# schema.net
KiCad netlist of a schematic drawn in EAGLE
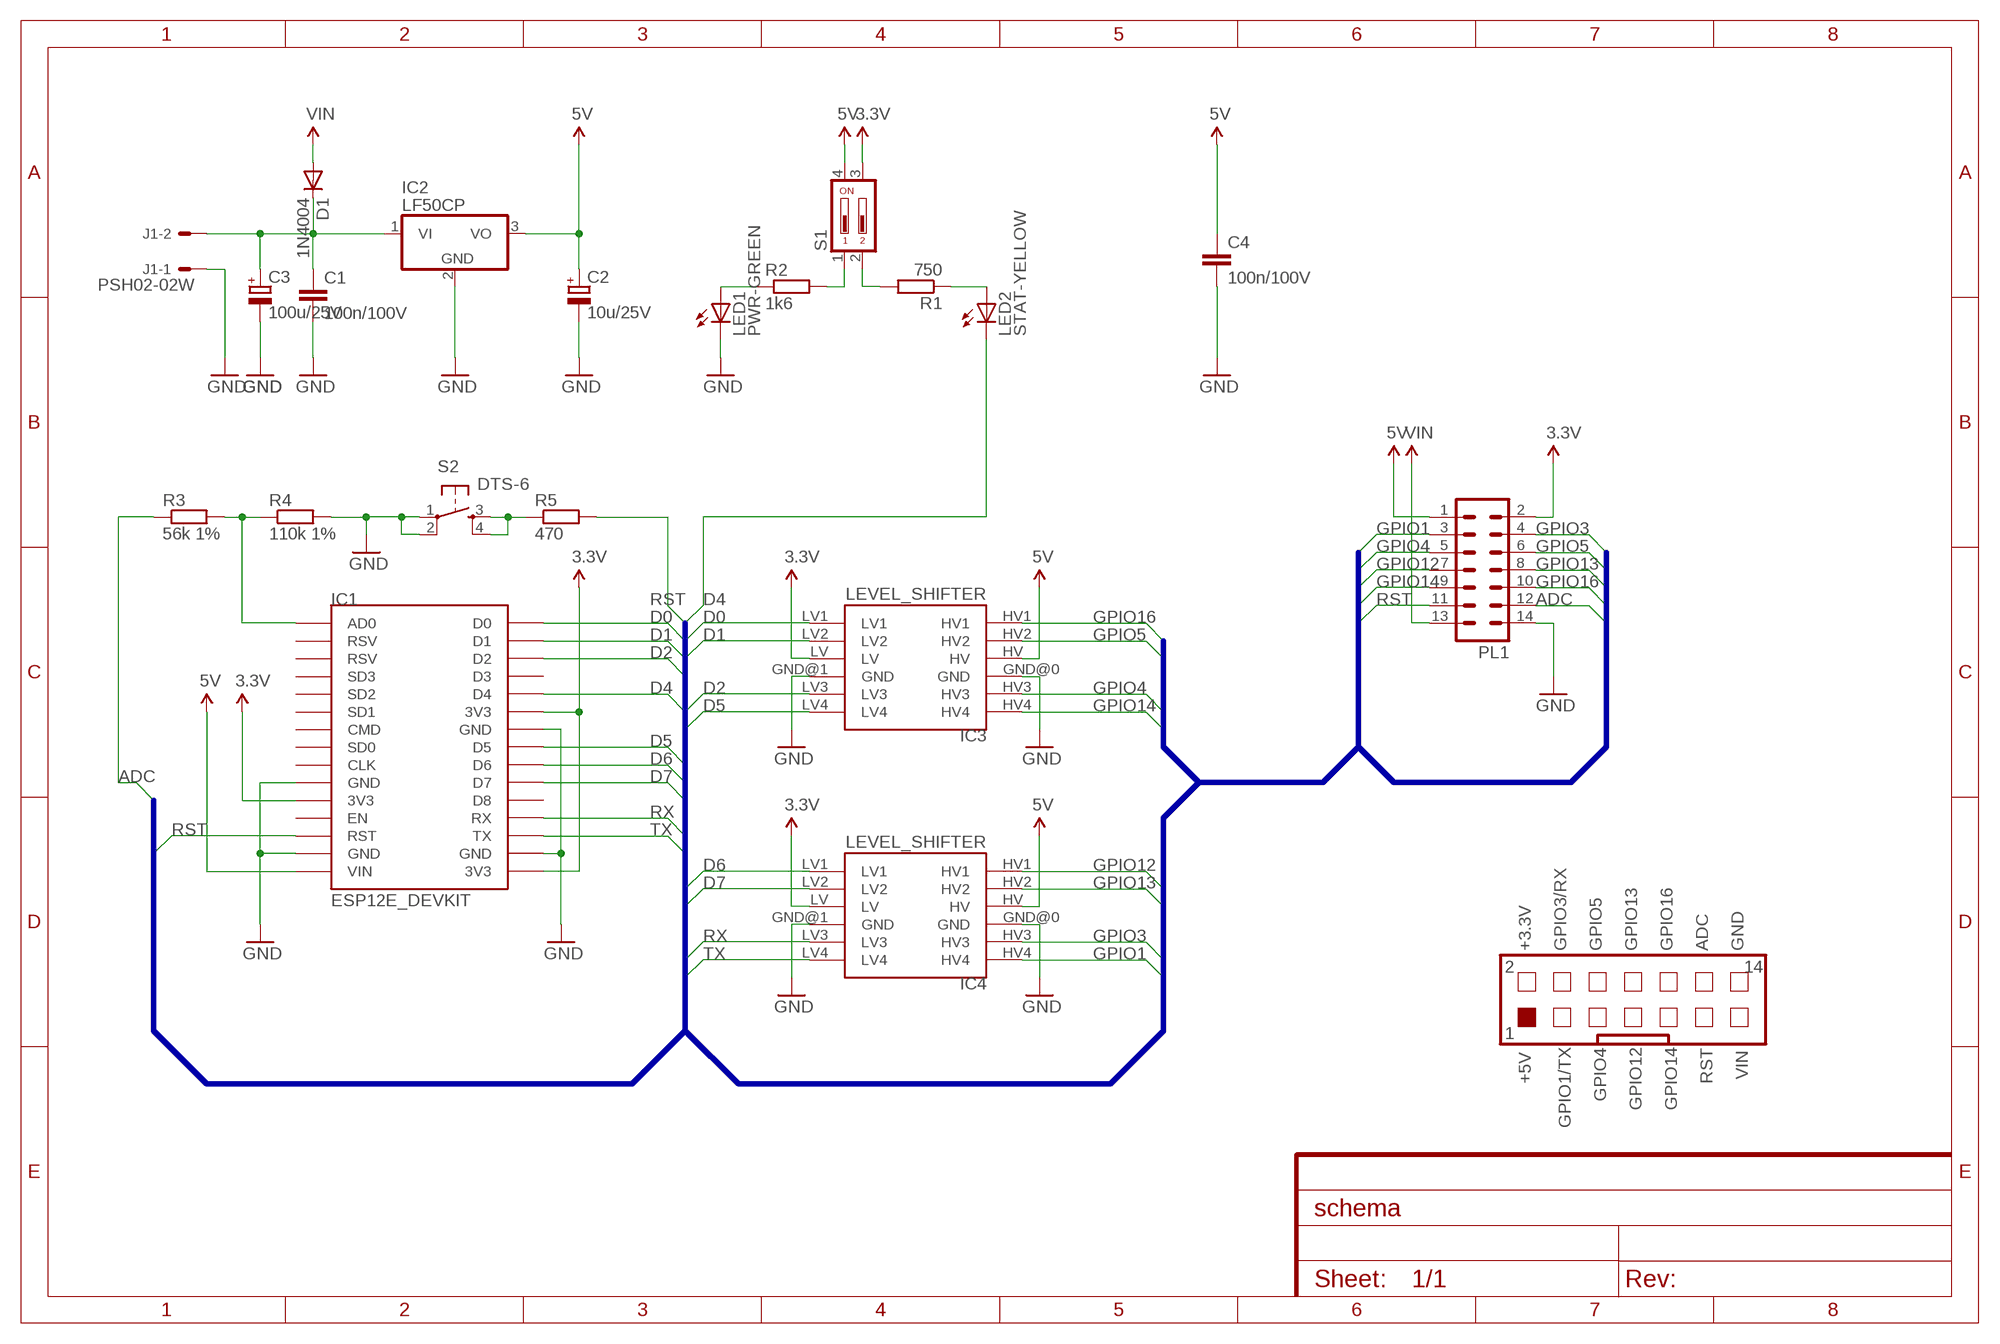
[diagram p0: schematic, sheet 1]

(export (version "E")
  (design (tool "Eeschema 10.0.6"))
  (components
    (comp (ref "C1")
      (value "100n/100V")
      (footprint "eagle-import:C025-025X050")
      (libsource (lib "eagle-import") (part "C-EUC025-025X050"))
    )
    (comp (ref "C2")
      (value "10u/25V")
      (footprint "eagle-import:E3,5-8")
      (libsource (lib "eagle-import") (part "CPOL-EUE3,5-8"))
    )
    (comp (ref "C3")
      (value "100u/25V")
      (footprint "eagle-import:E5-13")
      (libsource (lib "eagle-import") (part "CPOL-EUE5-13"))
    )
    (comp (ref "C4")
      (value "100n/100V")
      (footprint "eagle-import:C025-025X050")
      (libsource (lib "eagle-import") (part "C-EUC025-025X050"))
    )
    (comp (ref "D1")
      (value "1N4004")
      (footprint "eagle-import:DO41-10")
      (libsource (lib "eagle-import") (part "1N4004"))
    )
    (comp (ref "IC1")
      (value "ESP12E_DEVKIT")
      (footprint "eagle-import:ESP12E_DEVKIT")
      (libsource (lib "eagle-import") (part "ESP12E_DEVKIT"))
    )
    (comp (ref "IC2")
      (value "LF50CP")
      (footprint "eagle-import:TO220H")
      (libsource (lib "eagle-import") (part "LF50CP"))
    )
    (comp (ref "IC3")
      (value "LEVEL_SHIFTER")
      (footprint "eagle-import:LEVEL_SHIFTER")
      (libsource (lib "eagle-import") (part "LEVEL_SHIFTER"))
    )
    (comp (ref "IC4")
      (value "LEVEL_SHIFTER")
      (footprint "eagle-import:LEVEL_SHIFTER")
      (libsource (lib "eagle-import") (part "LEVEL_SHIFTER"))
    )
    (comp (ref "J1")
      (value "PSH02-02W")
      (footprint "eagle-import:7395-02")
      (libsource (lib "eagle-import") (part "22-?-0205-7028"))
    )
    (comp (ref "LED1")
      (value "PWR-GREEN")
      (footprint "eagle-import:LED3MM")
      (libsource (lib "eagle-import") (part "LED3MM"))
    )
    (comp (ref "LED2")
      (value "STAT-YELLOW")
      (footprint "eagle-import:LED3MM")
      (libsource (lib "eagle-import") (part "LED3MM"))
    )
    (comp (ref "PL1")
      (value "14V")
      (footprint "eagle-import:14V")
      (libsource (lib "eagle-import") (part "14V"))
    )
    (comp (ref "R1")
      (value "750")
      (footprint "eagle-import:R1206")
      (libsource (lib "eagle-import") (part "R-EU_R1206"))
    )
    (comp (ref "R2")
      (value "1k6")
      (footprint "eagle-import:R1206")
      (libsource (lib "eagle-import") (part "R-EU_R1206"))
    )
    (comp (ref "R3")
      (value "56k 1%")
      (footprint "eagle-import:R1206")
      (libsource (lib "eagle-import") (part "R-EU_R1206"))
    )
    (comp (ref "R4")
      (value "110k 1%")
      (footprint "eagle-import:R1206")
      (libsource (lib "eagle-import") (part "R-EU_R1206"))
    )
    (comp (ref "R5")
      (value "470")
      (footprint "eagle-import:R1206")
      (libsource (lib "eagle-import") (part "R-EU_R1206"))
    )
    (comp (ref "S1")
      (value "DIP02YL")
      (footprint "eagle-import:DIP02YL")
      (libsource (lib "eagle-import") (part "DIP02YL"))
    )
    (comp (ref "S2")
      (value "DTS-6")
      (footprint "eagle-import:DTS-6")
      (libsource (lib "eagle-import") (part "DTS-6"))
    )
  )
  (nets
    (net (code "1") (name "/ADC") (class "Default")
      (node (ref "PL1") (pin "12") (pinfunction "12_12") (pintype "passive"))
      (node (ref "R3") (pin "1") (pinfunction "1_1") (pintype "passive"))
    )
    (net (code "2") (name "/D0") (class "Default")
      (node (ref "IC1") (pin "D0") (pinfunction "D0_D0") (pintype "bidirectional"))
      (node (ref "IC3") (pin "LV1") (pinfunction "LV1_LV1") (pintype "bidirectional"))
    )
    (net (code "3") (name "/D1") (class "Default")
      (node (ref "IC1") (pin "D1") (pinfunction "D1_D1") (pintype "bidirectional"))
      (node (ref "IC3") (pin "LV2") (pinfunction "LV2_LV2") (pintype "bidirectional"))
    )
    (net (code "4") (name "/D2") (class "Default")
      (node (ref "IC1") (pin "D2") (pinfunction "D2_D2") (pintype "bidirectional"))
      (node (ref "IC3") (pin "LV3") (pinfunction "LV3_LV3") (pintype "bidirectional"))
    )
    (net (code "5") (name "/D4") (class "Default")
      (node (ref "IC1") (pin "D4") (pinfunction "D4_D4") (pintype "bidirectional"))
      (node (ref "LED2") (pin "K") (pinfunction "C_K") (pintype "passive"))
    )
    (net (code "6") (name "/D5") (class "Default")
      (node (ref "IC1") (pin "D5") (pinfunction "D5_D5") (pintype "bidirectional"))
      (node (ref "IC3") (pin "LV4") (pinfunction "LV4_LV4") (pintype "bidirectional"))
    )
    (net (code "7") (name "/D6") (class "Default")
      (node (ref "IC1") (pin "D6") (pinfunction "D6_D6") (pintype "bidirectional"))
      (node (ref "IC4") (pin "LV1") (pinfunction "LV1_LV1") (pintype "bidirectional"))
    )
    (net (code "8") (name "/D7") (class "Default")
      (node (ref "IC1") (pin "D7") (pinfunction "D7_D7") (pintype "bidirectional"))
      (node (ref "IC4") (pin "LV2") (pinfunction "LV2_LV2") (pintype "bidirectional"))
    )
    (net (code "9") (name "/GPIO1") (class "Default")
      (node (ref "IC4") (pin "HV4") (pinfunction "HV4_HV4") (pintype "bidirectional"))
      (node (ref "PL1") (pin "3") (pinfunction "3_3") (pintype "passive"))
    )
    (net (code "10") (name "/GPIO3") (class "Default")
      (node (ref "IC4") (pin "HV3") (pinfunction "HV3_HV3") (pintype "bidirectional"))
      (node (ref "PL1") (pin "4") (pinfunction "4_4") (pintype "passive"))
    )
    (net (code "11") (name "/GPIO4") (class "Default")
      (node (ref "IC3") (pin "HV3") (pinfunction "HV3_HV3") (pintype "bidirectional"))
      (node (ref "PL1") (pin "5") (pinfunction "5_5") (pintype "passive"))
    )
    (net (code "12") (name "/GPIO5") (class "Default")
      (node (ref "IC3") (pin "HV2") (pinfunction "HV2_HV2") (pintype "bidirectional"))
      (node (ref "PL1") (pin "6") (pinfunction "6_6") (pintype "passive"))
    )
    (net (code "13") (name "/GPIO12") (class "Default")
      (node (ref "IC4") (pin "HV1") (pinfunction "HV1_HV1") (pintype "bidirectional"))
      (node (ref "PL1") (pin "7") (pinfunction "7_7") (pintype "passive"))
    )
    (net (code "14") (name "/GPIO13") (class "Default")
      (node (ref "IC4") (pin "HV2") (pinfunction "HV2_HV2") (pintype "bidirectional"))
      (node (ref "PL1") (pin "8") (pinfunction "8_8") (pintype "passive"))
    )
    (net (code "15") (name "/GPIO14") (class "Default")
      (node (ref "IC3") (pin "HV4") (pinfunction "HV4_HV4") (pintype "bidirectional"))
      (node (ref "PL1") (pin "9") (pinfunction "9_9") (pintype "passive"))
    )
    (net (code "16") (name "/GPIO16") (class "Default")
      (node (ref "IC3") (pin "HV1") (pinfunction "HV1_HV1") (pintype "bidirectional"))
      (node (ref "PL1") (pin "10") (pinfunction "10_10") (pintype "passive"))
    )
    (net (code "17") (name "/RST") (class "Default")
      (node (ref "IC1") (pin "RST") (pinfunction "RST_RST") (pintype "bidirectional"))
      (node (ref "PL1") (pin "11") (pinfunction "11_11") (pintype "passive"))
      (node (ref "R5") (pin "2") (pinfunction "2_2") (pintype "passive"))
    )
    (net (code "18") (name "/RX") (class "Default")
      (node (ref "IC1") (pin "RX") (pinfunction "RX_RX") (pintype "bidirectional"))
      (node (ref "IC4") (pin "LV3") (pinfunction "LV3_LV3") (pintype "bidirectional"))
    )
    (net (code "19") (name "/TX") (class "Default")
      (node (ref "IC1") (pin "TX") (pinfunction "TX_TX") (pintype "bidirectional"))
      (node (ref "IC4") (pin "LV4") (pinfunction "LV4_LV4") (pintype "bidirectional"))
    )
    (net (code "20") (name "3.3V") (class "Default")
      (node (ref "IC1") (pin "3V3@0") (pinfunction "3V3_3V3@0") (pintype "bidirectional"))
      (node (ref "IC1") (pin "3V3@1") (pinfunction "3V3_3V3@1") (pintype "bidirectional"))
      (node (ref "IC1") (pin "3V3@2") (pinfunction "3V3_3V3@2") (pintype "bidirectional"))
      (node (ref "IC3") (pin "LV") (pinfunction "LV_LV") (pintype "bidirectional"))
      (node (ref "IC4") (pin "LV") (pinfunction "LV_LV") (pintype "bidirectional"))
      (node (ref "PL1") (pin "2") (pinfunction "2_2") (pintype "passive"))
      (node (ref "S1") (pin "3") (pinfunction "3_3") (pintype "passive"))
    )
    (net (code "21") (name "5V") (class "Default")
      (node (ref "C2") (pin "+") (pinfunction "+_+") (pintype "passive"))
      (node (ref "C4") (pin "1") (pinfunction "1_1") (pintype "passive"))
      (node (ref "IC1") (pin "VIN") (pinfunction "VIN_VIN") (pintype "bidirectional"))
      (node (ref "IC2") (pin "3") (pinfunction "VO_3") (pintype "passive"))
      (node (ref "IC3") (pin "HV") (pinfunction "HV_HV") (pintype "bidirectional"))
      (node (ref "IC4") (pin "HV") (pinfunction "HV_HV") (pintype "bidirectional"))
      (node (ref "PL1") (pin "1") (pinfunction "1_1") (pintype "passive"))
      (node (ref "S1") (pin "4") (pinfunction "4_4") (pintype "passive"))
    )
    (net (code "22") (name "GND") (class "Default")
      (node (ref "C1") (pin "2") (pinfunction "2_2") (pintype "passive"))
      (node (ref "C2") (pin "-") (pinfunction "-_-") (pintype "passive"))
      (node (ref "C3") (pin "-") (pinfunction "-_-") (pintype "passive"))
      (node (ref "C4") (pin "2") (pinfunction "2_2") (pintype "passive"))
      (node (ref "IC1") (pin "GND@0") (pinfunction "GND_GND@0") (pintype "bidirectional"))
      (node (ref "IC1") (pin "GND@1") (pinfunction "GND_GND@1") (pintype "bidirectional"))
      (node (ref "IC1") (pin "GND@2") (pinfunction "GND_GND@2") (pintype "bidirectional"))
      (node (ref "IC1") (pin "GND@3") (pinfunction "GND_GND@3") (pintype "bidirectional"))
      (node (ref "IC2") (pin "2") (pinfunction "GND_2") (pintype "passive"))
      (node (ref "IC3") (pin "GND@0") (pinfunction "GND_GND@0") (pintype "bidirectional"))
      (node (ref "IC3") (pin "GND@1") (pinfunction "GND_GND@1") (pintype "bidirectional"))
      (node (ref "IC4") (pin "GND@0") (pinfunction "GND_GND@0") (pintype "bidirectional"))
      (node (ref "IC4") (pin "GND@1") (pinfunction "GND_GND@1") (pintype "bidirectional"))
      (node (ref "J1") (pin "1") (pinfunction "S_1") (pintype "passive"))
      (node (ref "LED1") (pin "K") (pinfunction "C_K") (pintype "passive"))
      (node (ref "PL1") (pin "14") (pinfunction "14_14") (pintype "passive"))
      (node (ref "R4") (pin "2") (pinfunction "2_2") (pintype "passive"))
      (node (ref "S2") (pin "1") (pinfunction "1_1") (pintype "passive"))
      (node (ref "S2") (pin "2") (pinfunction "2_2") (pintype "passive"))
    )
    (net (code "23") (name "Net-(IC1-PadAD0)") (class "Default")
      (node (ref "IC1") (pin "AD0") (pinfunction "AD0_AD0") (pintype "bidirectional"))
      (node (ref "R3") (pin "2") (pinfunction "2_2") (pintype "passive"))
      (node (ref "R4") (pin "1") (pinfunction "1_1") (pintype "passive"))
    )
    (net (code "24") (name "Net-(IC2-VI)") (class "Default")
      (node (ref "C1") (pin "1") (pinfunction "1_1") (pintype "passive"))
      (node (ref "C3") (pin "+") (pinfunction "+_+") (pintype "passive"))
      (node (ref "D1") (pin "C") (pinfunction "C_C") (pintype "passive"))
      (node (ref "IC2") (pin "1") (pinfunction "VI_1") (pintype "input"))
      (node (ref "J1") (pin "2") (pinfunction "S_2") (pintype "passive"))
    )
    (net (code "25") (name "Net-(LED1-PadA)") (class "Default")
      (node (ref "LED1") (pin "A") (pinfunction "A_A") (pintype "passive"))
      (node (ref "R2") (pin "1") (pinfunction "1_1") (pintype "passive"))
    )
    (net (code "26") (name "Net-(LED2-PadA)") (class "Default")
      (node (ref "LED2") (pin "A") (pinfunction "A_A") (pintype "passive"))
      (node (ref "R1") (pin "1") (pinfunction "1_1") (pintype "passive"))
    )
    (net (code "27") (name "Net-(R1-Pad2)") (class "Default")
      (node (ref "R1") (pin "2") (pinfunction "2_2") (pintype "passive"))
      (node (ref "S1") (pin "2") (pinfunction "2_2") (pintype "passive"))
    )
    (net (code "28") (name "Net-(R2-Pad2)") (class "Default")
      (node (ref "R2") (pin "2") (pinfunction "2_2") (pintype "passive"))
      (node (ref "S1") (pin "1") (pinfunction "1_1") (pintype "passive"))
    )
    (net (code "29") (name "Net-(R5-Pad1)") (class "Default")
      (node (ref "R5") (pin "1") (pinfunction "1_1") (pintype "passive"))
      (node (ref "S2") (pin "3") (pinfunction "3_3") (pintype "passive"))
      (node (ref "S2") (pin "4") (pinfunction "4_4") (pintype "passive"))
    )
    (net (code "30") (name "VIN") (class "Default")
      (node (ref "D1") (pin "A") (pinfunction "A_A") (pintype "passive"))
      (node (ref "PL1") (pin "13") (pinfunction "13_13") (pintype "passive"))
    )
    (net (code "31") (name "unconnected-(IC1-PadCLK)") (class "Default")
      (node (ref "IC1") (pin "CLK") (pinfunction "CLK_CLK") (pintype "bidirectional"))
    )
    (net (code "32") (name "unconnected-(IC1-PadCMD)") (class "Default")
      (node (ref "IC1") (pin "CMD") (pinfunction "CMD_CMD") (pintype "bidirectional"))
    )
    (net (code "33") (name "unconnected-(IC1-PadD3)") (class "Default")
      (node (ref "IC1") (pin "D3") (pinfunction "D3_D3") (pintype "bidirectional"))
    )
    (net (code "34") (name "unconnected-(IC1-PadD8)") (class "Default")
      (node (ref "IC1") (pin "D8") (pinfunction "D8_D8") (pintype "bidirectional"))
    )
    (net (code "35") (name "unconnected-(IC1-PadEN)") (class "Default")
      (node (ref "IC1") (pin "EN") (pinfunction "EN_EN") (pintype "bidirectional"))
    )
    (net (code "36") (name "unconnected-(IC1-PadSD0)") (class "Default")
      (node (ref "IC1") (pin "SD0") (pinfunction "SD0_SD0") (pintype "bidirectional"))
    )
    (net (code "37") (name "unconnected-(IC1-PadSD1)") (class "Default")
      (node (ref "IC1") (pin "SD1") (pinfunction "SD1_SD1") (pintype "bidirectional"))
    )
    (net (code "38") (name "unconnected-(IC1-PadSD2)") (class "Default")
      (node (ref "IC1") (pin "SD2") (pinfunction "SD2_SD2") (pintype "bidirectional"))
    )
    (net (code "39") (name "unconnected-(IC1-PadSD3)") (class "Default")
      (node (ref "IC1") (pin "SD3") (pinfunction "SD3_SD3") (pintype "bidirectional"))
    )
    (net (code "40") (name "unconnected-(IC1-RSV-PadRSV@0)") (class "Default")
      (node (ref "IC1") (pin "RSV@0") (pinfunction "RSV_RSV@0") (pintype "bidirectional"))
    )
    (net (code "41") (name "unconnected-(IC1-RSV-PadRSV@1)") (class "Default")
      (node (ref "IC1") (pin "RSV@1") (pinfunction "RSV_RSV@1") (pintype "bidirectional"))
    )
  )
)
